# ludi_console_v1.net
KiCad netlist of a schematic drawn in Altium Designer
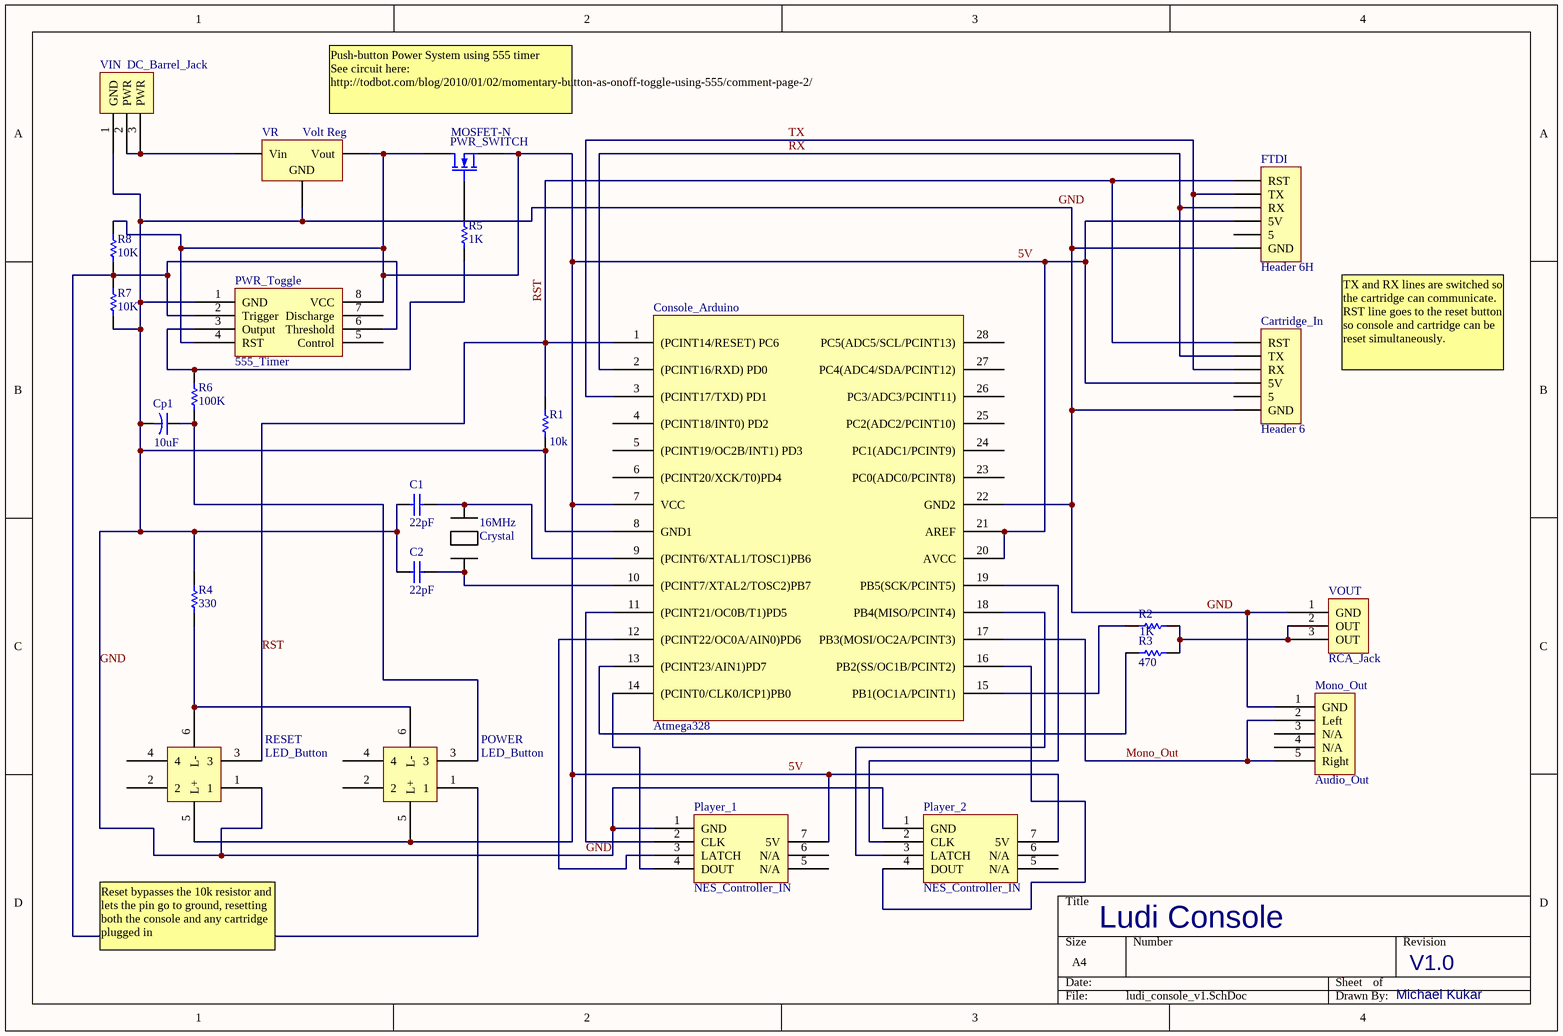
[diagram p0: ludi_console_v1.SchDoc]

(export (version "E")
  (design (tool "Eeschema 10.0.6"))
  (components
    (comp (ref "16MHz")
      (value "Crystal")
      (footprint "Crystal - duplicate")
      (libsource (lib "ludi_console_v1") (part "Crystal"))
    )
    (comp (ref "C1")
      (value "22pF")
      (footprint "RAD-0.3")
      (description "Capacitor")
      (fields (field (name "Comment") "Cap") (field (name "PUBLISHER") "Altium Limited"))
      (libsource (lib "Miscellaneous Devices") (part "Cap"))
    )
    (comp (ref "C2")
      (value "22pF")
      (footprint "RAD-0.3")
      (description "Capacitor")
      (fields (field (name "Comment") "Cap") (field (name "PUBLISHER") "Altium Limited"))
      (libsource (lib "Miscellaneous Devices") (part "Cap"))
    )
    (comp (ref "Cartridge_In")
      (value "Header 6")
      (footprint "HDR1X6")
      (description "Header, 6-Pin")
      (fields (field (name "PUBLISHER") "Altium Limited"))
      (libsource (lib "Miscellaneous Connectors") (part "Header 6"))
    )
    (comp (ref "Console_Arduino")
      (value "Atmega328")
      (footprint "DIP-28")
      (libsource (lib "ludi_v1") (part "Atmega328"))
    )
    (comp (ref "Cp1")
      (value "10uF")
      (footprint "CAPR5-4X5")
      (description "Capacitor")
      (fields (field (name "Comment") "Cap2") (field (name "PUBLISHER") "Altium Limited"))
      (libsource (lib "Miscellaneous Devices") (part "Cap2"))
    )
    (comp (ref "FTDI")
      (value "Header 6H")
      (footprint "HDR1X6H")
      (description "Header, 6-Pin, Right Angle")
      (fields (field (name "PUBLISHER") "Altium Limited"))
      (libsource (lib "Miscellaneous Connectors") (part "Header 6H"))
    )
    (comp (ref "Mono_Out") (value "Audio_Out") (libsource (lib "ludi_console_v1") (part "Audio_Out")))
    (comp (ref "Player_1")
      (value "NES_Controller_IN")
      (libsource (lib "ludi_console_v1") (part "NES_Controller_IN"))
    )
    (comp (ref "Player_2")
      (value "NES_Controller_IN")
      (libsource (lib "ludi_console_v1") (part "NES_Controller_IN"))
    )
    (comp (ref "POWER") (value "LED_Button") (libsource (lib "ludi_console_v1") (part "LED_Button")))
    (comp (ref "PWR_SWITCH")
      (value "MOSFET-N")
      (footprint "E3")
      (description "N-Channel MOSFET")
      (fields (field (name "PUBLISHER") "Altium Limited"))
      (libsource (lib "Miscellaneous Devices") (part "MOSFET-N"))
    )
    (comp (ref "PWR_Toggle") (value "555_Timer") (libsource (lib "ludi_console_v1") (part "555_Timer")))
    (comp (ref "R1")
      (value "10k")
      (footprint "AXIAL-0.3")
      (description "Resistor")
      (fields (field (name "Comment") "Res1") (field (name "PUBLISHER") "Altium Limited"))
      (libsource (lib "Miscellaneous Devices") (part "Res1"))
    )
    (comp (ref "R2")
      (value "1K")
      (footprint "AXIAL-0.3")
      (description "Resistor")
      (fields (field (name "Comment") "Res1") (field (name "PUBLISHER") "Altium Limited"))
      (libsource (lib "Miscellaneous Devices") (part "Res1"))
    )
    (comp (ref "R3")
      (value "470")
      (footprint "AXIAL-0.3")
      (description "Resistor")
      (fields (field (name "Comment") "Res1") (field (name "PUBLISHER") "Altium Limited"))
      (libsource (lib "Miscellaneous Devices") (part "Res1"))
    )
    (comp (ref "R4")
      (value "330")
      (footprint "AXIAL-0.3")
      (description "Resistor")
      (fields (field (name "Comment") "Res1") (field (name "PUBLISHER") "Altium Limited"))
      (libsource (lib "Miscellaneous Devices") (part "Res1"))
    )
    (comp (ref "R5")
      (value "1K")
      (footprint "AXIAL-0.3")
      (description "Resistor")
      (fields (field (name "Comment") "Res1") (field (name "PUBLISHER") "Altium Limited"))
      (libsource (lib "Miscellaneous Devices") (part "Res1"))
    )
    (comp (ref "R6")
      (value "100K")
      (footprint "AXIAL-0.3")
      (description "Resistor")
      (fields (field (name "Comment") "Res1") (field (name "PUBLISHER") "Altium Limited"))
      (libsource (lib "Miscellaneous Devices") (part "Res1"))
    )
    (comp (ref "R7")
      (value "10K")
      (footprint "AXIAL-0.3")
      (description "Resistor")
      (fields (field (name "Comment") "Res1") (field (name "PUBLISHER") "Altium Limited"))
      (libsource (lib "Miscellaneous Devices") (part "Res1"))
    )
    (comp (ref "R8")
      (value "10K")
      (footprint "AXIAL-0.3")
      (description "Resistor")
      (fields (field (name "Comment") "Res1") (field (name "PUBLISHER") "Altium Limited"))
      (libsource (lib "Miscellaneous Devices") (part "Res1"))
    )
    (comp (ref "RESET") (value "LED_Button") (libsource (lib "ludi_console_v1") (part "LED_Button")))
    (comp (ref "VIN") (value "DC_Barrel_Jack") (libsource (lib "ludi_console_v1") (part "DC_Barrel_Jack")))
    (comp (ref "VOUT")
      (value "RCA_Jack")
      (footprint "RCA_Jack")
      (libsource (lib "ludi_console_v1") (part "RCA_Jack"))
    )
    (comp (ref "VR")
      (value "Volt Reg")
      (footprint "D2PAK_L")
      (description "Voltage Regulator")
      (fields (field (name "PUBLISHER") "Altium Limited"))
      (libsource (lib "Miscellaneous Devices") (part "Volt Reg"))
    )
  )
  (nets
    (net (code "1") (name "/5V") (class "Default")
      (node (ref "Cartridge_In") (pin "4") (pinfunction "5V_4") (pintype "passive"))
      (node (ref "Console_Arduino") (pin "20") (pinfunction "AVCC_20") (pintype "passive"))
      (node (ref "Console_Arduino") (pin "21") (pinfunction "AREF_21") (pintype "passive"))
      (node (ref "Console_Arduino") (pin "7") (pinfunction "VCC_7") (pintype "passive"))
      (node (ref "FTDI") (pin "4") (pinfunction "5V_4") (pintype "passive"))
      (node (ref "POWER") (pin "5") (pinfunction "L+_5") (pintype "passive"))
      (node (ref "PWR_SWITCH") (pin "1") (pinfunction "D_1") (pintype "passive"))
      (node (ref "PWR_SWITCH") (pin "3") (pinfunction "S_3") (pintype "passive"))
      (node (ref "PWR_Toggle") (pin "4") (pinfunction "RST_4") (pintype "passive"))
      (node (ref "PWR_Toggle") (pin "8") (pinfunction "VCC_8") (pintype "passive"))
      (node (ref "Player_1") (pin "7") (pinfunction "5V_7") (pintype "passive"))
      (node (ref "Player_2") (pin "7") (pinfunction "5V_7") (pintype "passive"))
      (node (ref "R8") (pin "2") (pinfunction "2_2") (pintype "passive"))
      (node (ref "RESET") (pin "5") (pinfunction "L+_5") (pintype "passive"))
      (node (ref "VR") (pin "3") (pinfunction "Vout_3") (pintype "passive"))
    )
    (net (code "2") (name "/GND") (class "Default")
      (node (ref "C1") (pin "1") (pinfunction "1_1") (pintype "passive"))
      (node (ref "C2") (pin "1") (pinfunction "1_1") (pintype "passive"))
      (node (ref "Cartridge_In") (pin "6") (pinfunction "GND_6") (pintype "passive"))
      (node (ref "Console_Arduino") (pin "22") (pinfunction "GND2_22") (pintype "passive"))
      (node (ref "Console_Arduino") (pin "8") (pinfunction "GND1_8") (pintype "passive"))
      (node (ref "Cp1") (pin "2") (pinfunction "2_2") (pintype "passive"))
      (node (ref "FTDI") (pin "6") (pinfunction "GND_6") (pintype "passive"))
      (node (ref "Mono_Out") (pin "1") (pinfunction "GND_1") (pintype "passive"))
      (node (ref "PWR_Toggle") (pin "1") (pinfunction "GND_1") (pintype "passive"))
      (node (ref "Player_1") (pin "1") (pinfunction "GND_1") (pintype "passive"))
      (node (ref "Player_2") (pin "1") (pinfunction "GND_1") (pintype "passive"))
      (node (ref "R1") (pin "1") (pinfunction "1_1") (pintype "passive"))
      (node (ref "R4") (pin "2") (pinfunction "2_2") (pintype "passive"))
      (node (ref "R7") (pin "1") (pinfunction "1_1") (pintype "passive"))
      (node (ref "RESET") (pin "1") (pinfunction "1_1") (pintype "passive"))
      (node (ref "VIN") (pin "1") (pinfunction "GND_1") (pintype "passive"))
      (node (ref "VOUT") (pin "1") (pinfunction "GND_1") (pintype "passive"))
      (node (ref "VR") (pin "2") (pinfunction "GND_2") (pintype "passive"))
    )
    (net (code "3") (name "/Mono_Out") (class "Default")
      (node (ref "Console_Arduino") (pin "17") (pinfunction "PB3(MOSI/OC2A/PCINT3)_17") (pintype "passive"))
      (node (ref "Mono_Out") (pin "2") (pinfunction "Left_2") (pintype "passive"))
      (node (ref "Mono_Out") (pin "5") (pinfunction "Right_5") (pintype "passive"))
    )
    (net (code "4") (name "/RST") (class "Default")
      (node (ref "Cartridge_In") (pin "1") (pinfunction "RST_1") (pintype "passive"))
      (node (ref "Console_Arduino") (pin "1") (pinfunction "(PCINT14/RESET)_PC6_1") (pintype "passive"))
      (node (ref "FTDI") (pin "1") (pinfunction "RST_1") (pintype "passive"))
      (node (ref "R1") (pin "2") (pinfunction "2_2") (pintype "passive"))
      (node (ref "RESET") (pin "3") (pinfunction "3_3") (pintype "passive"))
    )
    (net (code "5") (name "/RX") (class "Default")
      (node (ref "Cartridge_In") (pin "2") (pinfunction "TX_2") (pintype "passive"))
      (node (ref "Console_Arduino") (pin "2") (pinfunction "(PCINT16/RXD)_PD0_2") (pintype "passive"))
      (node (ref "FTDI") (pin "3") (pinfunction "RX_3") (pintype "passive"))
    )
    (net (code "6") (name "/TX") (class "Default")
      (node (ref "Cartridge_In") (pin "3") (pinfunction "RX_3") (pintype "passive"))
      (node (ref "Console_Arduino") (pin "3") (pinfunction "(PCINT17/TXD)_PD1_3") (pintype "passive"))
      (node (ref "FTDI") (pin "2") (pinfunction "TX_2") (pintype "passive"))
    )
    (net (code "7") (name "Net-(16MHz-0)") (class "Default")
      (node (ref "16MHz") (pin "A") (pinfunction "0_A") (pintype "passive"))
      (node (ref "C2") (pin "2") (pinfunction "2_2") (pintype "passive"))
      (node (ref "Console_Arduino") (pin "10") (pinfunction "(PCINT7/XTAL2/TOSC2)PB7_10") (pintype "passive"))
    )
    (net (code "8") (name "Net-(16MHz-1)") (class "Default")
      (node (ref "16MHz") (pin "K") (pinfunction "1_K") (pintype "passive"))
      (node (ref "C1") (pin "2") (pinfunction "2_2") (pintype "passive"))
      (node (ref "Console_Arduino") (pin "9") (pinfunction "(PCINT6/XTAL1/TOSC1)PB6_9") (pintype "passive"))
    )
    (net (code "9") (name "Net-(Console_Arduino-(PCINT0{slash}CLK0{slash}ICP1)PB0)") (class "Default")
      (node (ref "Console_Arduino") (pin "14") (pinfunction "(PCINT0/CLK0/ICP1)PB0_14") (pintype "passive"))
      (node (ref "Player_1") (pin "4") (pinfunction "DOUT_4") (pintype "passive"))
    )
    (net (code "10") (name "Net-(Console_Arduino-(PCINT21{slash}OC0B{slash}T1)PD5)") (class "Default")
      (node (ref "Console_Arduino") (pin "11") (pinfunction "(PCINT21/OC0B/T1)PD5_11") (pintype "passive"))
      (node (ref "Player_1") (pin "2") (pinfunction "CLK_2") (pintype "passive"))
    )
    (net (code "11") (name "Net-(Console_Arduino-(PCINT22{slash}OC0A{slash}AIN0)PD6)") (class "Default")
      (node (ref "Console_Arduino") (pin "12") (pinfunction "(PCINT22/OC0A/AIN0)PD6_12") (pintype "passive"))
      (node (ref "Player_1") (pin "3") (pinfunction "LATCH_3") (pintype "passive"))
    )
    (net (code "12") (name "Net-(Console_Arduino-(PCINT23{slash}AIN1)PD7)") (class "Default")
      (node (ref "Console_Arduino") (pin "13") (pinfunction "(PCINT23/AIN1)PD7_13") (pintype "passive"))
      (node (ref "R3") (pin "1") (pinfunction "1_1") (pintype "passive"))
    )
    (net (code "13") (name "Net-(Console_Arduino-PB1(OC1A{slash}PCINT1))") (class "Default")
      (node (ref "Console_Arduino") (pin "15") (pinfunction "PB1(OC1A/PCINT1)_15") (pintype "passive"))
      (node (ref "R2") (pin "1") (pinfunction "1_1") (pintype "passive"))
    )
    (net (code "14") (name "Net-(Console_Arduino-PB2(SS{slash}OC1B{slash}PCINT2))") (class "Default")
      (node (ref "Console_Arduino") (pin "16") (pinfunction "PB2(SS/OC1B/PCINT2)_16") (pintype "passive"))
      (node (ref "Player_2") (pin "4") (pinfunction "DOUT_4") (pintype "passive"))
    )
    (net (code "15") (name "Net-(Console_Arduino-PB4(MISO{slash}PCINT4))") (class "Default")
      (node (ref "Console_Arduino") (pin "18") (pinfunction "PB4(MISO/PCINT4)_18") (pintype "passive"))
      (node (ref "Player_2") (pin "3") (pinfunction "LATCH_3") (pintype "passive"))
    )
    (net (code "16") (name "Net-(Console_Arduino-PB5(SCK{slash}PCINT5))") (class "Default")
      (node (ref "Console_Arduino") (pin "19") (pinfunction "PB5(SCK/PCINT5)_19") (pintype "passive"))
      (node (ref "Player_2") (pin "2") (pinfunction "CLK_2") (pintype "passive"))
    )
    (net (code "17") (name "Net-(Cp1-Pad1)") (class "Default")
      (node (ref "Cp1") (pin "1") (pinfunction "1_1") (pintype "passive"))
      (node (ref "POWER") (pin "3") (pinfunction "3_3") (pintype "passive"))
      (node (ref "R6") (pin "1") (pinfunction "1_1") (pintype "passive"))
    )
    (net (code "18") (name "Net-(POWER-L-)") (class "Default")
      (node (ref "POWER") (pin "6") (pinfunction "L-_6") (pintype "passive"))
      (node (ref "R4") (pin "1") (pinfunction "1_1") (pintype "passive"))
      (node (ref "RESET") (pin "6") (pinfunction "L-_6") (pintype "passive"))
    )
    (net (code "19") (name "Net-(PWR_SWITCH-G)") (class "Default")
      (node (ref "PWR_SWITCH") (pin "2") (pinfunction "G_2") (pintype "passive"))
      (node (ref "R5") (pin "2") (pinfunction "2_2") (pintype "passive"))
    )
    (net (code "20") (name "Net-(PWR_Toggle-Output)") (class "Default")
      (node (ref "PWR_Toggle") (pin "3") (pinfunction "Output_3") (pintype "passive"))
      (node (ref "R5") (pin "1") (pinfunction "1_1") (pintype "passive"))
      (node (ref "R6") (pin "2") (pinfunction "2_2") (pintype "passive"))
    )
    (net (code "21") (name "Net-(PWR_Toggle-Threshold)") (class "Default")
      (node (ref "POWER") (pin "1") (pinfunction "1_1") (pintype "passive"))
      (node (ref "PWR_Toggle") (pin "2") (pinfunction "Trigger_2") (pintype "passive"))
      (node (ref "PWR_Toggle") (pin "6") (pinfunction "Threshold_6") (pintype "passive"))
      (node (ref "R7") (pin "2") (pinfunction "2_2") (pintype "passive"))
      (node (ref "R8") (pin "1") (pinfunction "1_1") (pintype "passive"))
    )
    (net (code "22") (name "Net-(R2-Pad2)") (class "Default")
      (node (ref "R2") (pin "2") (pinfunction "2_2") (pintype "passive"))
      (node (ref "R3") (pin "2") (pinfunction "2_2") (pintype "passive"))
      (node (ref "VOUT") (pin "2") (pinfunction "OUT_2") (pintype "passive"))
      (node (ref "VOUT") (pin "3") (pinfunction "OUT_3") (pintype "passive"))
    )
    (net (code "23") (name "Net-(VR-Vin)") (class "Default")
      (node (ref "VIN") (pin "2") (pinfunction "PWR_2") (pintype "passive"))
      (node (ref "VIN") (pin "3") (pinfunction "PWR_3") (pintype "passive"))
      (node (ref "VR") (pin "1") (pinfunction "Vin_1") (pintype "passive"))
    )
    (net (code "24") (name "unconnected-(Cartridge_In-Pad5)") (class "Default")
      (node (ref "Cartridge_In") (pin "5") (pinfunction "5_5") (pintype "passive"))
    )
    (net (code "25") (name "unconnected-(Console_Arduino-(PCINT18{slash}INT0)_PD2-Pad4)") (class "Default")
      (node (ref "Console_Arduino") (pin "4") (pinfunction "(PCINT18/INT0)_PD2_4") (pintype "passive"))
    )
    (net (code "26") (name "unconnected-(Console_Arduino-(PCINT19{slash}OC2B{slash}INT1)_PD3-Pad5)") (class "Default")
      (node (ref "Console_Arduino") (pin "5") (pinfunction "(PCINT19/OC2B/INT1)_PD3_5") (pintype "passive"))
    )
    (net (code "27") (name "unconnected-(Console_Arduino-(PCINT20{slash}XCK{slash}T0)PD4-Pad6)") (class "Default")
      (node (ref "Console_Arduino") (pin "6") (pinfunction "(PCINT20/XCK/T0)PD4_6") (pintype "passive"))
    )
    (net (code "28") (name "unconnected-(Console_Arduino-PC0(ADC0{slash}PCINT8)-Pad23)") (class "Default")
      (node (ref "Console_Arduino") (pin "23") (pinfunction "PC0(ADC0/PCINT8)_23") (pintype "passive"))
    )
    (net (code "29") (name "unconnected-(Console_Arduino-PC1(ADC1{slash}PCINT9)-Pad24)") (class "Default")
      (node (ref "Console_Arduino") (pin "24") (pinfunction "PC1(ADC1/PCINT9)_24") (pintype "passive"))
    )
    (net (code "30") (name "unconnected-(Console_Arduino-PC2(ADC2{slash}PCINT10)-Pad25)") (class "Default")
      (node (ref "Console_Arduino") (pin "25") (pinfunction "PC2(ADC2/PCINT10)_25") (pintype "passive"))
    )
    (net (code "31") (name "unconnected-(Console_Arduino-PC3{slash}ADC3{slash}PCINT11)-Pad26)") (class "Default")
      (node (ref "Console_Arduino") (pin "26") (pinfunction "PC3/ADC3/PCINT11)_26") (pintype "passive"))
    )
    (net (code "32") (name "unconnected-(Console_Arduino-PC4(ADC4{slash}SDA{slash}PCINT12)-Pad27)") (class "Default")
      (node (ref "Console_Arduino") (pin "27") (pinfunction "PC4(ADC4/SDA/PCINT12)_27") (pintype "passive"))
    )
    (net (code "33") (name "unconnected-(Console_Arduino-PC5(ADC5{slash}SCL{slash}PCINT13)-Pad28)") (class "Default")
      (node (ref "Console_Arduino") (pin "28") (pinfunction "PC5(ADC5/SCL/PCINT13)_28") (pintype "passive"))
    )
    (net (code "34") (name "unconnected-(FTDI-Pad5)") (class "Default")
      (node (ref "FTDI") (pin "5") (pinfunction "5_5") (pintype "passive"))
    )
    (net (code "35") (name "unconnected-(Mono_Out-N{slash}A-Pad3)") (class "Default")
      (node (ref "Mono_Out") (pin "3") (pinfunction "N/A_3") (pintype "passive"))
    )
    (net (code "36") (name "unconnected-(Mono_Out-N{slash}A-Pad4)") (class "Default")
      (node (ref "Mono_Out") (pin "4") (pinfunction "N/A_4") (pintype "passive"))
    )
    (net (code "37") (name "unconnected-(POWER-Pad2)") (class "Default")
      (node (ref "POWER") (pin "2") (pinfunction "2_2") (pintype "passive"))
    )
    (net (code "38") (name "unconnected-(POWER-Pad4)") (class "Default")
      (node (ref "POWER") (pin "4") (pinfunction "4_4") (pintype "passive"))
    )
    (net (code "39") (name "unconnected-(PWR_Toggle-Control-Pad5)") (class "Default")
      (node (ref "PWR_Toggle") (pin "5") (pinfunction "Control_5") (pintype "passive"))
    )
    (net (code "40") (name "unconnected-(PWR_Toggle-Discharge-Pad7)") (class "Default")
      (node (ref "PWR_Toggle") (pin "7") (pinfunction "Discharge_7") (pintype "passive"))
    )
    (net (code "41") (name "unconnected-(Player_1-N{slash}A-Pad5)") (class "Default")
      (node (ref "Player_1") (pin "5") (pinfunction "N/A_5") (pintype "passive"))
    )
    (net (code "42") (name "unconnected-(Player_1-N{slash}A-Pad6)") (class "Default")
      (node (ref "Player_1") (pin "6") (pinfunction "N/A_6") (pintype "passive"))
    )
    (net (code "43") (name "unconnected-(Player_2-N{slash}A-Pad5)") (class "Default")
      (node (ref "Player_2") (pin "5") (pinfunction "N/A_5") (pintype "passive"))
    )
    (net (code "44") (name "unconnected-(Player_2-N{slash}A-Pad6)") (class "Default")
      (node (ref "Player_2") (pin "6") (pinfunction "N/A_6") (pintype "passive"))
    )
    (net (code "45") (name "unconnected-(RESET-Pad2)") (class "Default")
      (node (ref "RESET") (pin "2") (pinfunction "2_2") (pintype "passive"))
    )
    (net (code "46") (name "unconnected-(RESET-Pad4)") (class "Default")
      (node (ref "RESET") (pin "4") (pinfunction "4_4") (pintype "passive"))
    )
  )
)
